# DDR3_Regulators.net
KiCad netlist of a schematic drawn in Altium Designer
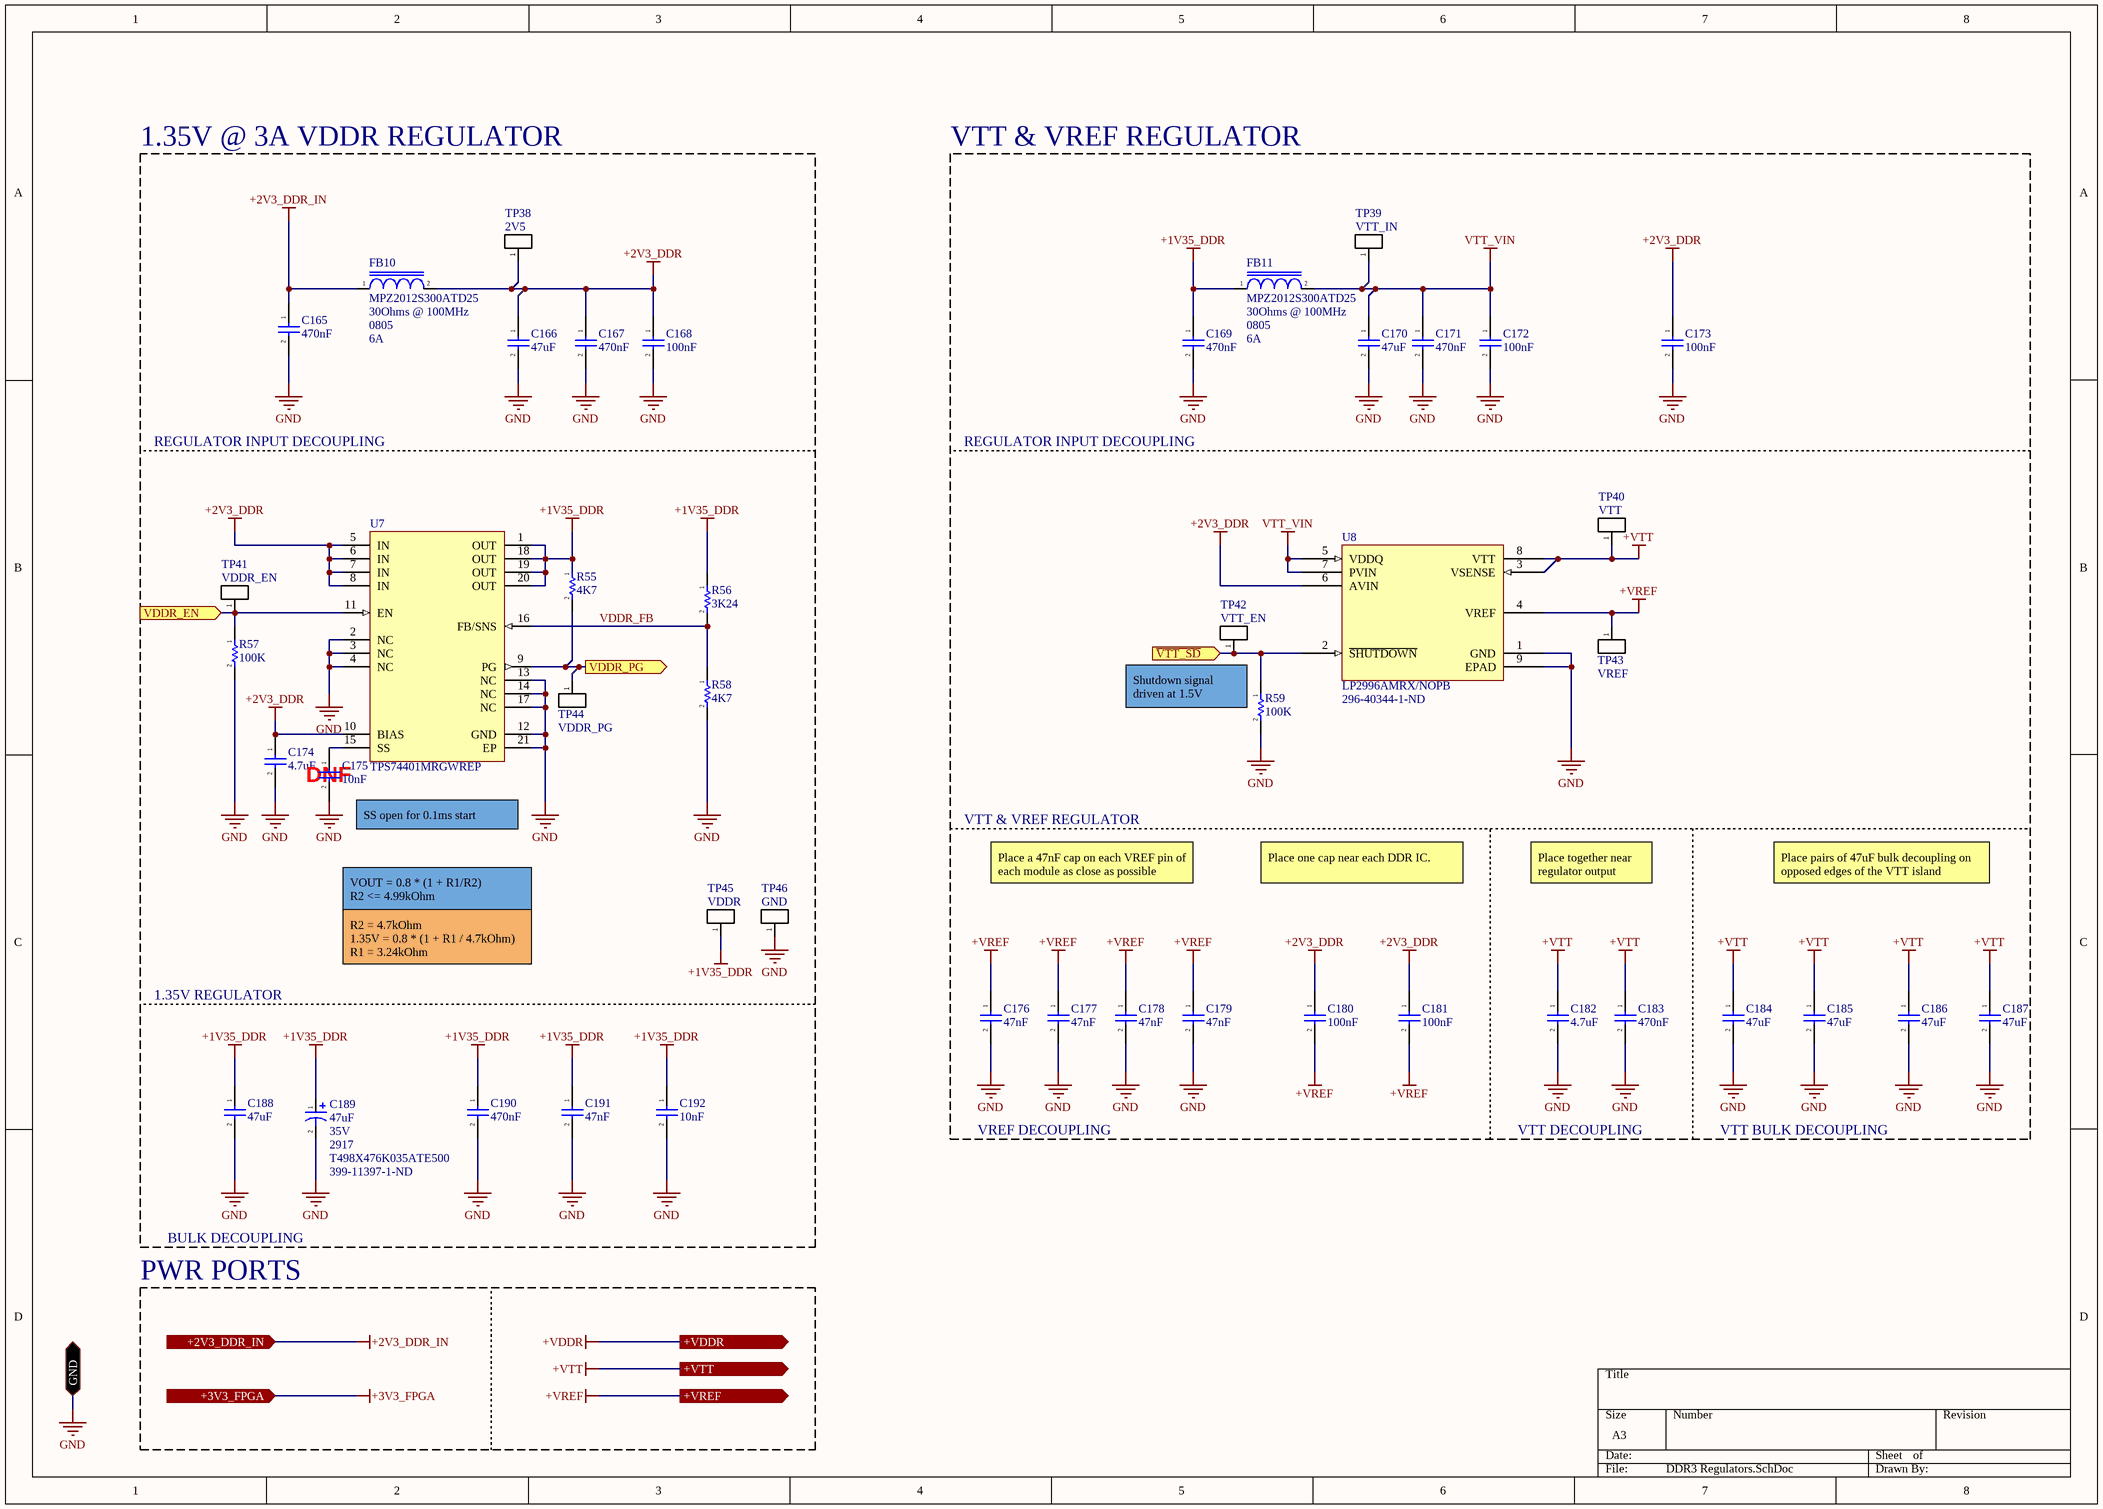
[diagram p0: DDR3 Regulators.SchDoc]

(export (version "E")
  (design (tool "Eeschema 10.0.6"))
  (components
    (comp (ref "C165")
      (value "470nF")
      (footprint "CAP_0402")
      (description "Generic SMT Ceramic Capacitor")
      (libsource (lib "Symbols") (part "CAP_CER"))
    )
    (comp (ref "C166")
      (value "47uF")
      (footprint "CAP_1206")
      (description "Generic SMT Ceramic Capacitor")
      (libsource (lib "Symbols") (part "CAP_CER"))
    )
    (comp (ref "C167")
      (value "470nF")
      (footprint "CAP_0402")
      (description "Generic SMT Ceramic Capacitor")
      (libsource (lib "Symbols") (part "CAP_CER"))
    )
    (comp (ref "C168")
      (value "100nF")
      (footprint "CAP_0402")
      (description "Generic SMT Ceramic Capacitor")
      (libsource (lib "Symbols") (part "CAP_CER"))
    )
    (comp (ref "C169")
      (value "470nF")
      (footprint "CAP_0402")
      (description "Generic SMT Ceramic Capacitor")
      (libsource (lib "Symbols") (part "CAP_CER"))
    )
    (comp (ref "C170")
      (value "47uF")
      (footprint "CAP_1206")
      (description "Generic SMT Ceramic Capacitor")
      (libsource (lib "Symbols") (part "CAP_CER"))
    )
    (comp (ref "C171")
      (value "470nF")
      (footprint "CAP_0402")
      (description "Generic SMT Ceramic Capacitor")
      (libsource (lib "Symbols") (part "CAP_CER"))
    )
    (comp (ref "C172")
      (value "100nF")
      (footprint "CAP_0402")
      (description "Generic SMT Ceramic Capacitor")
      (libsource (lib "Symbols") (part "CAP_CER"))
    )
    (comp (ref "C173")
      (value "100nF")
      (footprint "CAP_0402")
      (description "Generic SMT Ceramic Capacitor")
      (libsource (lib "Symbols") (part "CAP_CER"))
    )
    (comp (ref "C174")
      (value "4.7uF")
      (footprint "CAP_0805")
      (description "Generic SMT Ceramic Capacitor")
      (libsource (lib "Symbols") (part "CAP_CER"))
    )
    (comp (ref "C175")
      (value "10nF")
      (footprint "CAP_0201")
      (description "Generic SMT Ceramic Capacitor")
      (libsource (lib "Symbols") (part "CAP_CER"))
    )
    (comp (ref "C176")
      (value "47nF")
      (footprint "CAP_0201")
      (description "Generic SMT Ceramic Capacitor")
      (libsource (lib "Symbols") (part "CAP_CER"))
    )
    (comp (ref "C177")
      (value "47nF")
      (footprint "CAP_0201")
      (description "Generic SMT Ceramic Capacitor")
      (libsource (lib "Symbols") (part "CAP_CER"))
    )
    (comp (ref "C178")
      (value "47nF")
      (footprint "CAP_0201")
      (description "Generic SMT Ceramic Capacitor")
      (libsource (lib "Symbols") (part "CAP_CER"))
    )
    (comp (ref "C179")
      (value "47nF")
      (footprint "CAP_0201")
      (description "Generic SMT Ceramic Capacitor")
      (libsource (lib "Symbols") (part "CAP_CER"))
    )
    (comp (ref "C180")
      (value "100nF")
      (footprint "CAP_0402")
      (description "Generic SMT Ceramic Capacitor")
      (libsource (lib "Symbols") (part "CAP_CER"))
    )
    (comp (ref "C181")
      (value "100nF")
      (footprint "CAP_0402")
      (description "Generic SMT Ceramic Capacitor")
      (libsource (lib "Symbols") (part "CAP_CER"))
    )
    (comp (ref "C182")
      (value "4.7uF")
      (footprint "CAP_0805")
      (description "Generic SMT Ceramic Capacitor")
      (libsource (lib "Symbols") (part "CAP_CER"))
    )
    (comp (ref "C183")
      (value "470nF")
      (footprint "CAP_0402")
      (description "Generic SMT Ceramic Capacitor")
      (libsource (lib "Symbols") (part "CAP_CER"))
    )
    (comp (ref "C184")
      (value "47uF")
      (footprint "CAP_1206")
      (description "Generic SMT Ceramic Capacitor")
      (libsource (lib "Symbols") (part "CAP_CER"))
    )
    (comp (ref "C185")
      (value "47uF")
      (footprint "CAP_1206")
      (description "Generic SMT Ceramic Capacitor")
      (libsource (lib "Symbols") (part "CAP_CER"))
    )
    (comp (ref "C186")
      (value "47uF")
      (footprint "CAP_1206")
      (description "Generic SMT Ceramic Capacitor")
      (libsource (lib "Symbols") (part "CAP_CER"))
    )
    (comp (ref "C187")
      (value "47uF")
      (footprint "CAP_1206")
      (description "Generic SMT Ceramic Capacitor")
      (libsource (lib "Symbols") (part "CAP_CER"))
    )
    (comp (ref "C188")
      (value "47uF")
      (footprint "CAP_1206")
      (description "Generic SMT Ceramic Capacitor")
      (libsource (lib "Symbols") (part "CAP_CER"))
    )
    (comp (ref "C189")
      (value "47uF")
      (footprint "CAP_2917_P")
      (description "47 µF Molded Tantalum Capacitors 35 V 2917 (7343 Metric) 500mOhm")
      (fields
        (field (name "MFR") "KEMET")
        (field (name "TOLERANCE") "10%")
        (field (name "PART #") "T498X476K035ATE500")
        (field (name "RATED VOLTAGE") "35V")
        (field (name "SUPPLIER PART NUMBER 1") "399-11397-1-ND")
        (field (name "PACKAGE") "2917")
      )
      (libsource (lib "CryptLib") (part "CAP_T498X476K035ATE500"))
    )
    (comp (ref "C190")
      (value "470nF")
      (footprint "CAP_0402")
      (description "Generic SMT Ceramic Capacitor")
      (libsource (lib "Symbols") (part "CAP_CER"))
    )
    (comp (ref "C191")
      (value "47nF")
      (footprint "CAP_0201")
      (description "Generic SMT Ceramic Capacitor")
      (libsource (lib "Symbols") (part "CAP_CER"))
    )
    (comp (ref "C192")
      (value "10nF")
      (footprint "CAP_0201")
      (description "Generic SMT Ceramic Capacitor")
      (libsource (lib "Symbols") (part "CAP_CER"))
    )
    (comp (ref "FB10")
      (value "MPZ2012S300ATD25")
      (footprint "IND_0805")
      (description "30 Ohms @ 100 MHz 1 Power Line Ferrite Bead 0805 (2012 Metric) 6A 10mOhm")
      (fields
        (field (name "IMPEDANCE @ FREQ") "30Ohms @ 100MHz")
        (field (name "PACKAGE / CASE") "0805")
        (field (name "CURRENT RATING") "6A")
      )
      (libsource (lib "CryptLib") (part "IND_MPZ2012S300ATD25"))
    )
    (comp (ref "FB11")
      (value "MPZ2012S300ATD25")
      (footprint "IND_0805")
      (description "30 Ohms @ 100 MHz 1 Power Line Ferrite Bead 0805 (2012 Metric) 6A 10mOhm")
      (fields
        (field (name "IMPEDANCE @ FREQ") "30Ohms @ 100MHz")
        (field (name "PACKAGE / CASE") "0805")
        (field (name "CURRENT RATING") "6A")
      )
      (libsource (lib "CryptLib") (part "IND_MPZ2012S300ATD25"))
    )
    (comp (ref "R55")
      (value "4K7")
      (footprint "RES_0603")
      (description "Resistor")
      (fields (field (name "POWER") "1/16W") (field (name "TOLERANCE") "10%"))
      (libsource (lib "Symbols") (part "RESISTOR"))
    )
    (comp (ref "R56")
      (value "3K24")
      (footprint "RES_0603")
      (description "Resistor")
      (fields (field (name "POWER") "1/16W") (field (name "TOLERANCE") "2%"))
      (libsource (lib "Symbols") (part "RESISTOR"))
    )
    (comp (ref "R57")
      (value "100K")
      (footprint "RES_0603")
      (description "Resistor")
      (fields (field (name "POWER") "1/16W") (field (name "TOLERANCE") "10%"))
      (libsource (lib "Symbols") (part "RESISTOR"))
    )
    (comp (ref "R58")
      (value "4K7")
      (footprint "RES_0603")
      (description "Resistor")
      (fields (field (name "POWER") "1/16W") (field (name "TOLERANCE") "10%"))
      (libsource (lib "Symbols") (part "RESISTOR"))
    )
    (comp (ref "R59")
      (value "100K")
      (footprint "RES_0603")
      (description "Resistor")
      (fields (field (name "POWER") "1/16W") (field (name "TOLERANCE") "10%"))
      (libsource (lib "Symbols") (part "RESISTOR"))
    )
    (comp (ref "TP38")
      (value "2V5")
      (footprint "TP_HOLE")
      (description "Test Point")
      (libsource (lib "Symbols") (part "TESTPOINT"))
    )
    (comp (ref "TP39")
      (value "VTT_IN")
      (footprint "TP_PAD")
      (description "Test Point")
      (libsource (lib "Symbols") (part "TESTPOINT"))
    )
    (comp (ref "TP40")
      (value "VTT")
      (footprint "TP_PAD")
      (description "Test Point")
      (libsource (lib "Symbols") (part "TESTPOINT"))
    )
    (comp (ref "TP41")
      (value "VDDR_EN")
      (footprint "TP_PAD_TINY")
      (description "Test Point")
      (libsource (lib "Symbols") (part "TESTPOINT"))
    )
    (comp (ref "TP42")
      (value "VTT_EN")
      (footprint "TP_PAD_TINY")
      (description "Test Point")
      (libsource (lib "Symbols") (part "TESTPOINT"))
    )
    (comp (ref "TP43")
      (value "VREF")
      (footprint "TP_PAD")
      (description "Test Point")
      (libsource (lib "Symbols") (part "TESTPOINT"))
    )
    (comp (ref "TP44")
      (value "VDDR_PG")
      (footprint "TP_PAD_TINY")
      (description "Test Point")
      (libsource (lib "Symbols") (part "TESTPOINT"))
    )
    (comp (ref "TP45")
      (value "VDDR")
      (footprint "TP_HOLE")
      (description "Test Point")
      (libsource (lib "Symbols") (part "TESTPOINT"))
    )
    (comp (ref "TP46")
      (value "GND")
      (footprint "TP_PAD_SMALL")
      (description "Test Point")
      (libsource (lib "Symbols") (part "TESTPOINT"))
    )
    (comp (ref "U7")
      (value "TPS74401MRGWREP")
      (footprint "TPS74401")
      (description "IC REG LINEAR POS ADJ 3A 20VQFN")
      (fields (field (name "MFR") "Texas Instruments") (field (name "DIGIKEY PART NUMBER") "296-27227-1-ND"))
      (libsource (lib "CryptLib") (part "IC_TPS47701"))
    )
    (comp (ref "U8")
      (value "LP2996AMRX/NOPB")
      (footprint "LP2996AMRX")
      (description "IC REGULATOR DDR TERM 8SOPWRPAD")
      (fields
        (field (name "MFR") "Texas Instruments")
        (field (name "SUPPLIER PART NUMBER 1") "296-40344-1-ND")
      )
      (libsource (lib "CryptLib") (part "IC_LP2996AMRX"))
    )
  )
  (nets
    (net (code "1") (name "+1V35_DDR") (class "Default")
      (node (ref "C169") (pin "1") (pinfunction "1_1") (pintype "passive"))
      (node (ref "C188") (pin "1") (pinfunction "1_1") (pintype "passive"))
      (node (ref "C189") (pin "1") (pinfunction "1_1") (pintype "passive"))
      (node (ref "C190") (pin "1") (pinfunction "1_1") (pintype "passive"))
      (node (ref "C191") (pin "1") (pinfunction "1_1") (pintype "passive"))
      (node (ref "C192") (pin "1") (pinfunction "1_1") (pintype "passive"))
      (node (ref "FB11") (pin "1") (pinfunction "1_1") (pintype "passive"))
      (node (ref "R55") (pin "1") (pinfunction "1_1") (pintype "passive"))
      (node (ref "R56") (pin "1") (pinfunction "1_1") (pintype "passive"))
      (node (ref "TP45") (pin "1") (pinfunction "A_1") (pintype "passive"))
      (node (ref "U7") (pin "1") (pinfunction "OUT_1") (pintype "power_in"))
      (node (ref "U7") (pin "18") (pinfunction "OUT_18") (pintype "power_in"))
      (node (ref "U7") (pin "19") (pinfunction "OUT_19") (pintype "power_in"))
      (node (ref "U7") (pin "20") (pinfunction "OUT_20") (pintype "power_in"))
    )
    (net (code "2") (name "+2V3_DDR") (class "Default")
      (node (ref "C166") (pin "1") (pinfunction "1_1") (pintype "passive"))
      (node (ref "C167") (pin "1") (pinfunction "1_1") (pintype "passive"))
      (node (ref "C168") (pin "1") (pinfunction "1_1") (pintype "passive"))
      (node (ref "C173") (pin "1") (pinfunction "1_1") (pintype "passive"))
      (node (ref "C174") (pin "1") (pinfunction "1_1") (pintype "passive"))
      (node (ref "C180") (pin "1") (pinfunction "1_1") (pintype "passive"))
      (node (ref "C181") (pin "1") (pinfunction "1_1") (pintype "passive"))
      (node (ref "FB10") (pin "2") (pinfunction "2_2") (pintype "passive"))
      (node (ref "TP38") (pin "1") (pinfunction "A_1") (pintype "passive"))
      (node (ref "U7") (pin "10") (pinfunction "BIAS_10") (pintype "power_in"))
      (node (ref "U7") (pin "5") (pinfunction "IN_5") (pintype "power_in"))
      (node (ref "U7") (pin "6") (pinfunction "IN_6") (pintype "power_in"))
      (node (ref "U7") (pin "7") (pinfunction "IN_7") (pintype "power_in"))
      (node (ref "U7") (pin "8") (pinfunction "IN_8") (pintype "power_in"))
      (node (ref "U8") (pin "6") (pinfunction "AVIN_6") (pintype "power_in"))
    )
    (net (code "3") (name "+2V3_DDR_IN") (class "Default")
      (node (ref "C165") (pin "1") (pinfunction "1_1") (pintype "passive"))
      (node (ref "FB10") (pin "1") (pinfunction "1_1") (pintype "passive"))
    )
    (net (code "6") (name "+VREF") (class "Default")
      (node (ref "C176") (pin "1") (pinfunction "1_1") (pintype "passive"))
      (node (ref "C177") (pin "1") (pinfunction "1_1") (pintype "passive"))
      (node (ref "C178") (pin "1") (pinfunction "1_1") (pintype "passive"))
      (node (ref "C179") (pin "1") (pinfunction "1_1") (pintype "passive"))
      (node (ref "C180") (pin "2") (pinfunction "2_2") (pintype "passive"))
      (node (ref "C181") (pin "2") (pinfunction "2_2") (pintype "passive"))
      (node (ref "TP43") (pin "1") (pinfunction "A_1") (pintype "passive"))
      (node (ref "U8") (pin "4") (pinfunction "VREF_4") (pintype "power_in"))
    )
    (net (code "7") (name "+VTT") (class "Default")
      (node (ref "C182") (pin "1") (pinfunction "1_1") (pintype "passive"))
      (node (ref "C183") (pin "1") (pinfunction "1_1") (pintype "passive"))
      (node (ref "C184") (pin "1") (pinfunction "1_1") (pintype "passive"))
      (node (ref "C185") (pin "1") (pinfunction "1_1") (pintype "passive"))
      (node (ref "C186") (pin "1") (pinfunction "1_1") (pintype "passive"))
      (node (ref "C187") (pin "1") (pinfunction "1_1") (pintype "passive"))
      (node (ref "TP40") (pin "1") (pinfunction "A_1") (pintype "passive"))
      (node (ref "U8") (pin "3") (pinfunction "VSENSE_3") (pintype "input"))
      (node (ref "U8") (pin "8") (pinfunction "VTT_8") (pintype "power_in"))
    )
    (net (code "8") (name "/VDDR_EN") (class "Default")
      (node (ref "R57") (pin "1") (pinfunction "1_1") (pintype "passive"))
      (node (ref "TP41") (pin "1") (pinfunction "A_1") (pintype "passive"))
      (node (ref "U7") (pin "11") (pinfunction "EN_11") (pintype "input"))
    )
    (net (code "9") (name "/VDDR_FB") (class "Default")
      (node (ref "R56") (pin "2") (pinfunction "2_2") (pintype "passive"))
      (node (ref "R58") (pin "1") (pinfunction "1_1") (pintype "passive"))
      (node (ref "U7") (pin "16") (pinfunction "FB/SNS_16") (pintype "input"))
    )
    (net (code "10") (name "/VDDR_PG") (class "Default")
      (node (ref "R55") (pin "2") (pinfunction "2_2") (pintype "passive"))
      (node (ref "TP44") (pin "1") (pinfunction "A_1") (pintype "passive"))
      (node (ref "U7") (pin "9") (pinfunction "PG_9") (pintype "output"))
    )
    (net (code "11") (name "/VTT_SD") (class "Default")
      (node (ref "R59") (pin "1") (pinfunction "1_1") (pintype "passive"))
      (node (ref "TP42") (pin "1") (pinfunction "A_1") (pintype "passive"))
      (node (ref "U8") (pin "2") (pinfunction "~{SHUTDOWN}_2") (pintype "input"))
    )
    (net (code "12") (name "GND") (class "Default")
      (node (ref "C165") (pin "2") (pinfunction "2_2") (pintype "passive"))
      (node (ref "C166") (pin "2") (pinfunction "2_2") (pintype "passive"))
      (node (ref "C167") (pin "2") (pinfunction "2_2") (pintype "passive"))
      (node (ref "C168") (pin "2") (pinfunction "2_2") (pintype "passive"))
      (node (ref "C169") (pin "2") (pinfunction "2_2") (pintype "passive"))
      (node (ref "C170") (pin "2") (pinfunction "2_2") (pintype "passive"))
      (node (ref "C171") (pin "2") (pinfunction "2_2") (pintype "passive"))
      (node (ref "C172") (pin "2") (pinfunction "2_2") (pintype "passive"))
      (node (ref "C173") (pin "2") (pinfunction "2_2") (pintype "passive"))
      (node (ref "C174") (pin "2") (pinfunction "2_2") (pintype "passive"))
      (node (ref "C175") (pin "2") (pinfunction "2_2") (pintype "passive"))
      (node (ref "C176") (pin "2") (pinfunction "2_2") (pintype "passive"))
      (node (ref "C177") (pin "2") (pinfunction "2_2") (pintype "passive"))
      (node (ref "C178") (pin "2") (pinfunction "2_2") (pintype "passive"))
      (node (ref "C179") (pin "2") (pinfunction "2_2") (pintype "passive"))
      (node (ref "C182") (pin "2") (pinfunction "2_2") (pintype "passive"))
      (node (ref "C183") (pin "2") (pinfunction "2_2") (pintype "passive"))
      (node (ref "C184") (pin "2") (pinfunction "2_2") (pintype "passive"))
      (node (ref "C185") (pin "2") (pinfunction "2_2") (pintype "passive"))
      (node (ref "C186") (pin "2") (pinfunction "2_2") (pintype "passive"))
      (node (ref "C187") (pin "2") (pinfunction "2_2") (pintype "passive"))
      (node (ref "C188") (pin "2") (pinfunction "2_2") (pintype "passive"))
      (node (ref "C189") (pin "2") (pinfunction "2_2") (pintype "passive"))
      (node (ref "C190") (pin "2") (pinfunction "2_2") (pintype "passive"))
      (node (ref "C191") (pin "2") (pinfunction "2_2") (pintype "passive"))
      (node (ref "C192") (pin "2") (pinfunction "2_2") (pintype "passive"))
      (node (ref "R57") (pin "2") (pinfunction "2_2") (pintype "passive"))
      (node (ref "R58") (pin "2") (pinfunction "2_2") (pintype "passive"))
      (node (ref "R59") (pin "2") (pinfunction "2_2") (pintype "passive"))
      (node (ref "TP46") (pin "1") (pinfunction "A_1") (pintype "passive"))
      (node (ref "U7") (pin "12") (pinfunction "GND_12") (pintype "power_in"))
      (node (ref "U7") (pin "13") (pinfunction "NC_13") (pintype "passive"))
      (node (ref "U7") (pin "14") (pinfunction "NC_14") (pintype "passive"))
      (node (ref "U7") (pin "17") (pinfunction "NC_17") (pintype "passive"))
      (node (ref "U7") (pin "2") (pinfunction "NC_2") (pintype "passive"))
      (node (ref "U7") (pin "21") (pinfunction "EP_21") (pintype "power_in"))
      (node (ref "U7") (pin "3") (pinfunction "NC_3") (pintype "passive"))
      (node (ref "U7") (pin "4") (pinfunction "NC_4") (pintype "passive"))
      (node (ref "U8") (pin "1") (pinfunction "GND_1") (pintype "power_in"))
      (node (ref "U8") (pin "9") (pinfunction "EPAD_9") (pintype "power_in"))
    )
    (net (code "13") (name "Net-(U7-SS)") (class "Default")
      (node (ref "C175") (pin "1") (pinfunction "1_1") (pintype "passive"))
      (node (ref "U7") (pin "15") (pinfunction "SS_15") (pintype "passive"))
    )
    (net (code "14") (name "VTT_VIN") (class "Default")
      (node (ref "C170") (pin "1") (pinfunction "1_1") (pintype "passive"))
      (node (ref "C171") (pin "1") (pinfunction "1_1") (pintype "passive"))
      (node (ref "C172") (pin "1") (pinfunction "1_1") (pintype "passive"))
      (node (ref "FB11") (pin "2") (pinfunction "2_2") (pintype "passive"))
      (node (ref "TP39") (pin "1") (pinfunction "A_1") (pintype "passive"))
      (node (ref "U8") (pin "5") (pinfunction "VDDQ_5") (pintype "input"))
      (node (ref "U8") (pin "7") (pinfunction "PVIN_7") (pintype "power_in"))
    )
  )
)
